# esp8266_button.net
KiCad netlist of a schematic drawn in EAGLE
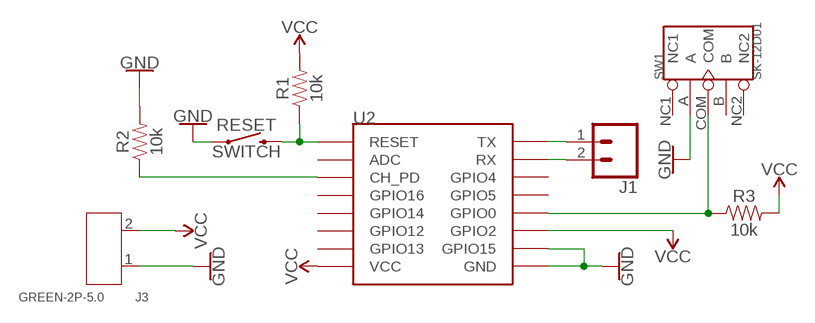
[diagram p0: schematic, sheet 1]

(export (version "E")
  (design (tool "Eeschema 10.0.6"))
  (components
    (comp (ref "J1")
      (value "CONN_02")
      (footprint "eagle-import:1X02")
      (libsource (lib "eagle-import") (part "CONN_02"))
    )
    (comp (ref "J3")
      (value "GREEN-2P-5.0")
      (footprint "eagle-import:H2-5.0-10.5X8.0MM")
      (libsource (lib "eagle-import") (part "SCREW-TERMINAL-GREEN(2P-5.0)"))
    )
    (comp (ref "R1")
      (value "10k")
      (footprint "eagle-import:AXIAL-0.3")
      (libsource (lib "eagle-import") (part "10KOHM-HORIZ-1/4W-5%"))
    )
    (comp (ref "R2")
      (value "10k")
      (footprint "eagle-import:AXIAL-0.3")
      (libsource (lib "eagle-import") (part "10KOHM-HORIZ-1/4W-5%"))
    )
    (comp (ref "R3")
      (value "10k")
      (footprint "eagle-import:AXIAL-0.3")
      (libsource (lib "eagle-import") (part "10KOHM-HORIZ-1/4W-5%"))
    )
    (comp (ref "RESET")
      (value "SWITCH")
      (footprint "eagle-import:TACTILE_SWITCH_PTH_6.0MM")
      (libsource (lib "eagle-import") (part "MOMENTARY-SWITCH-SPST-PTH-6.0MM"))
    )
    (comp (ref "SW1")
      (value "SK-12D01")
      (footprint "eagle-import:SW5-2.0-8.8X4.4X4.7MM-90D")
      (libsource (lib "eagle-import") (part "DIP-TOGGLE-SWITCH-ON-ON(3+2P-8.8X4.6MM)"))
    )
    (comp (ref "U2")
      (value "ESP12SMD")
      (footprint "eagle-import:ESP12-SMD")
      (libsource (lib "eagle-import") (part "ESP12SMD"))
    )
  )
  (nets
    (net (code "1") (name "GND") (class "Default")
      (node (ref "J3") (pin "1") (pinfunction "1_1") (pintype "bidirectional"))
      (node (ref "R2") (pin "P$2") (pinfunction "2_P$2") (pintype "passive"))
      (node (ref "RESET") (pin "1") (pinfunction "1_1") (pintype "passive"))
      (node (ref "SW1") (pin "A") (pinfunction "A_A") (pintype "bidirectional"))
      (node (ref "U2") (pin "GND") (pinfunction "GND_GND") (pintype "bidirectional"))
      (node (ref "U2") (pin "GPIO15") (pinfunction "GPIO15_GPIO15") (pintype "bidirectional"))
    )
    (net (code "2") (name "Net-(R1-1)") (class "Default")
      (node (ref "R1") (pin "P$1") (pinfunction "1_P$1") (pintype "passive"))
      (node (ref "RESET") (pin "3") (pinfunction "2_3") (pintype "passive"))
      (node (ref "U2") (pin "RESET") (pinfunction "RESET_RESET") (pintype "bidirectional"))
    )
    (net (code "3") (name "Net-(R2-1)") (class "Default")
      (node (ref "R2") (pin "P$1") (pinfunction "1_P$1") (pintype "passive"))
      (node (ref "U2") (pin "CH_PD") (pinfunction "CH_PD_CH_PD") (pintype "bidirectional"))
    )
    (net (code "4") (name "Net-(R3-1)") (class "Default")
      (node (ref "R3") (pin "P$1") (pinfunction "1_P$1") (pintype "passive"))
      (node (ref "SW1") (pin "COM") (pinfunction "COM_COM") (pintype "bidirectional"))
      (node (ref "U2") (pin "GPIO0") (pinfunction "GPIO0_GPIO0") (pintype "bidirectional"))
    )
    (net (code "5") (name "Net-(U2-RX)") (class "Default")
      (node (ref "J1") (pin "2") (pinfunction "2_2") (pintype "passive"))
      (node (ref "U2") (pin "RXD0") (pinfunction "RX_RXD0") (pintype "bidirectional"))
    )
    (net (code "6") (name "Net-(U2-TX)") (class "Default")
      (node (ref "J1") (pin "1") (pinfunction "1_1") (pintype "passive"))
      (node (ref "U2") (pin "TXD0") (pinfunction "TX_TXD0") (pintype "bidirectional"))
    )
    (net (code "7") (name "VCC") (class "Default")
      (node (ref "J3") (pin "2") (pinfunction "2_2") (pintype "bidirectional"))
      (node (ref "R1") (pin "P$2") (pinfunction "2_P$2") (pintype "passive"))
      (node (ref "R3") (pin "P$2") (pinfunction "2_P$2") (pintype "passive"))
      (node (ref "U2") (pin "GPIO2") (pinfunction "GPIO2_GPIO2") (pintype "bidirectional"))
      (node (ref "U2") (pin "VCC") (pinfunction "VCC_VCC") (pintype "bidirectional"))
    )
    (net (code "8") (name "unconnected-(SW1-PadB)") (class "Default")
      (node (ref "SW1") (pin "B") (pinfunction "B_B") (pintype "bidirectional"))
    )
    (net (code "9") (name "unconnected-(SW1-PadNC1)") (class "Default")
      (node (ref "SW1") (pin "NC1") (pinfunction "NC1_NC1") (pintype "bidirectional"))
    )
    (net (code "10") (name "unconnected-(SW1-PadNC2)") (class "Default")
      (node (ref "SW1") (pin "NC2") (pinfunction "NC2_NC2") (pintype "bidirectional"))
    )
    (net (code "11") (name "unconnected-(U2-PadADC)") (class "Default")
      (node (ref "U2") (pin "ADC") (pinfunction "ADC_ADC") (pintype "bidirectional"))
    )
    (net (code "12") (name "unconnected-(U2-PadGPIO4)") (class "Default")
      (node (ref "U2") (pin "GPIO4") (pinfunction "GPIO4_GPIO4") (pintype "bidirectional"))
    )
    (net (code "13") (name "unconnected-(U2-PadGPIO5)") (class "Default")
      (node (ref "U2") (pin "GPIO5") (pinfunction "GPIO5_GPIO5") (pintype "bidirectional"))
    )
    (net (code "14") (name "unconnected-(U2-PadGPIO12)") (class "Default")
      (node (ref "U2") (pin "GPIO12") (pinfunction "GPIO12_GPIO12") (pintype "bidirectional"))
    )
    (net (code "15") (name "unconnected-(U2-PadGPIO13)") (class "Default")
      (node (ref "U2") (pin "GPIO13") (pinfunction "GPIO13_GPIO13") (pintype "bidirectional"))
    )
    (net (code "16") (name "unconnected-(U2-PadGPIO14)") (class "Default")
      (node (ref "U2") (pin "GPIO14") (pinfunction "GPIO14_GPIO14") (pintype "bidirectional"))
    )
    (net (code "17") (name "unconnected-(U2-PadGPIO16)") (class "Default")
      (node (ref "U2") (pin "GPIO16") (pinfunction "GPIO16_GPIO16") (pintype "bidirectional"))
    )
  )
)
